# Projeck_telur.net
KiCad netlist of a schematic drawn in EAGLE
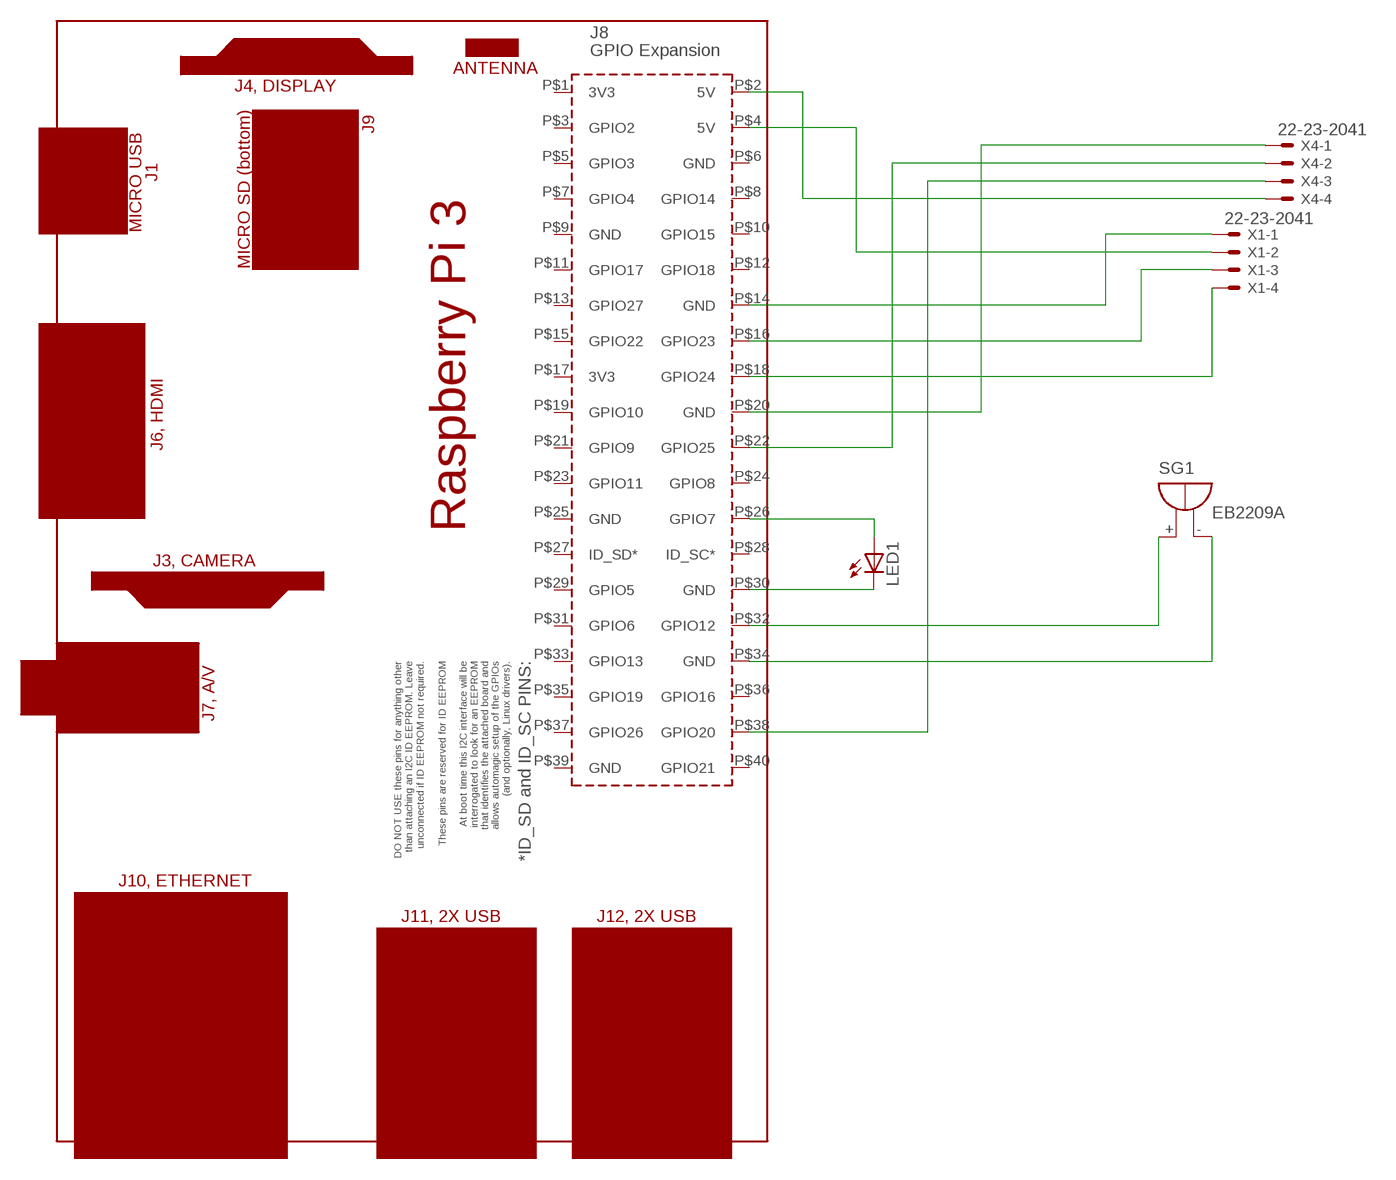
[diagram p0: schematic, sheet 1]

(export (version "E")
  (design (tool "Eeschema 10.0.6"))
  (components
    (comp (ref "LED1")
      (value "LEDB152")
      (footprint "eagle-import:Q62902-B152")
      (libsource (lib "eagle-import") (part "LEDB152"))
    )
    (comp (ref "PCB1")
      (value "RPI3")
      (footprint "eagle-import:RPI3")
      (libsource (lib "eagle-import") (part "RPI3"))
    )
    (comp (ref "SG1")
      (value "EB2209A")
      (footprint "eagle-import:EB2209A")
      (libsource (lib "eagle-import") (part "EB2209A"))
    )
    (comp (ref "X1")
      (value "22-23-2041")
      (footprint "eagle-import:22-23-2041")
      (fields (field (name "MF") "MOLEX"))
      (libsource (lib "eagle-import") (part "22-23-2041"))
    )
    (comp (ref "X4")
      (value "22-23-2041")
      (footprint "eagle-import:22-23-2041")
      (fields (field (name "MF") "MOLEX"))
      (libsource (lib "eagle-import") (part "22-23-2041"))
    )
  )
  (nets
    (net (code "1") (name "Net-(LED1-C)") (class "Default")
      (node (ref "LED1") (pin "K") (pinfunction "C_K") (pintype "passive"))
      (node (ref "PCB1") (pin "P$30") (pinfunction "GND_P$30") (pintype "bidirectional"))
    )
    (net (code "2") (name "Net-(PCB1-GND-PadP$34)") (class "Default")
      (node (ref "PCB1") (pin "P$34") (pinfunction "GND_P$34") (pintype "bidirectional"))
      (node (ref "SG1") (pin "-") (pinfunction "-_-") (pintype "passive"))
    )
    (net (code "3") (name "Net-(PCB1-GPIO7)") (class "Default")
      (node (ref "LED1") (pin "A") (pinfunction "A_A") (pintype "passive"))
      (node (ref "PCB1") (pin "P$26") (pinfunction "GPIO7_P$26") (pintype "bidirectional"))
    )
    (net (code "4") (name "Net-(PCB1-GPIO12)") (class "Default")
      (node (ref "PCB1") (pin "P$32") (pinfunction "GPIO12_P$32") (pintype "bidirectional"))
      (node (ref "SG1") (pin "+") (pinfunction "+_+") (pintype "passive"))
    )
    (net (code "5") (name "Net-(PCB1-GPIO20)") (class "Default")
      (node (ref "PCB1") (pin "P$38") (pinfunction "GPIO20_P$38") (pintype "bidirectional"))
      (node (ref "X4") (pin "3") (pinfunction "S_3") (pintype "passive"))
    )
    (net (code "6") (name "Net-(PCB1-GPIO23)") (class "Default")
      (node (ref "PCB1") (pin "P$16") (pinfunction "GPIO23_P$16") (pintype "bidirectional"))
      (node (ref "X1") (pin "3") (pinfunction "S_3") (pintype "passive"))
    )
    (net (code "7") (name "Net-(PCB1-GPIO24)") (class "Default")
      (node (ref "PCB1") (pin "P$18") (pinfunction "GPIO24_P$18") (pintype "bidirectional"))
      (node (ref "X1") (pin "4") (pinfunction "S_4") (pintype "passive"))
    )
    (net (code "8") (name "Net-(PCB1-GPIO25)") (class "Default")
      (node (ref "PCB1") (pin "P$22") (pinfunction "GPIO25_P$22") (pintype "bidirectional"))
      (node (ref "X4") (pin "2") (pinfunction "S_2") (pintype "passive"))
    )
    (net (code "9") (name "Net-(X1A-S)") (class "Default")
      (node (ref "PCB1") (pin "P$14") (pinfunction "GND_P$14") (pintype "bidirectional"))
      (node (ref "X1") (pin "1") (pinfunction "S_1") (pintype "passive"))
    )
    (net (code "10") (name "Net-(X1B-S)") (class "Default")
      (node (ref "PCB1") (pin "P$4") (pinfunction "5V_P$4") (pintype "bidirectional"))
      (node (ref "X1") (pin "2") (pinfunction "S_2") (pintype "passive"))
    )
    (net (code "11") (name "Net-(X4A-S)") (class "Default")
      (node (ref "PCB1") (pin "P$20") (pinfunction "GND_P$20") (pintype "bidirectional"))
      (node (ref "X4") (pin "1") (pinfunction "S_1") (pintype "passive"))
    )
    (net (code "12") (name "Net-(X4D-S)") (class "Default")
      (node (ref "PCB1") (pin "P$2") (pinfunction "5V_P$2") (pintype "bidirectional"))
      (node (ref "X4") (pin "4") (pinfunction "S_4") (pintype "passive"))
    )
    (net (code "13") (name "unconnected-(PCB1-3V3-PadP$1)") (class "Default")
      (node (ref "PCB1") (pin "P$1") (pinfunction "3V3_P$1") (pintype "bidirectional"))
    )
    (net (code "14") (name "unconnected-(PCB1-3V3-PadP$17)") (class "Default")
      (node (ref "PCB1") (pin "P$17") (pinfunction "3V3_P$17") (pintype "bidirectional"))
    )
    (net (code "15") (name "unconnected-(PCB1-GND-PadP$6)") (class "Default")
      (node (ref "PCB1") (pin "P$6") (pinfunction "GND_P$6") (pintype "bidirectional"))
    )
    (net (code "16") (name "unconnected-(PCB1-GND-PadP$9)") (class "Default")
      (node (ref "PCB1") (pin "P$9") (pinfunction "GND_P$9") (pintype "bidirectional"))
    )
    (net (code "17") (name "unconnected-(PCB1-GND-PadP$25)") (class "Default")
      (node (ref "PCB1") (pin "P$25") (pinfunction "GND_P$25") (pintype "bidirectional"))
    )
    (net (code "18") (name "unconnected-(PCB1-GND-PadP$39)") (class "Default")
      (node (ref "PCB1") (pin "P$39") (pinfunction "GND_P$39") (pintype "bidirectional"))
    )
    (net (code "19") (name "unconnected-(PCB1-GPIO2-PadP$3)") (class "Default")
      (node (ref "PCB1") (pin "P$3") (pinfunction "GPIO2_P$3") (pintype "bidirectional"))
    )
    (net (code "20") (name "unconnected-(PCB1-GPIO3-PadP$5)") (class "Default")
      (node (ref "PCB1") (pin "P$5") (pinfunction "GPIO3_P$5") (pintype "bidirectional"))
    )
    (net (code "21") (name "unconnected-(PCB1-GPIO4-PadP$7)") (class "Default")
      (node (ref "PCB1") (pin "P$7") (pinfunction "GPIO4_P$7") (pintype "bidirectional"))
    )
    (net (code "22") (name "unconnected-(PCB1-GPIO5-PadP$29)") (class "Default")
      (node (ref "PCB1") (pin "P$29") (pinfunction "GPIO5_P$29") (pintype "bidirectional"))
    )
    (net (code "23") (name "unconnected-(PCB1-GPIO6-PadP$31)") (class "Default")
      (node (ref "PCB1") (pin "P$31") (pinfunction "GPIO6_P$31") (pintype "bidirectional"))
    )
    (net (code "24") (name "unconnected-(PCB1-GPIO8-PadP$24)") (class "Default")
      (node (ref "PCB1") (pin "P$24") (pinfunction "GPIO8_P$24") (pintype "bidirectional"))
    )
    (net (code "25") (name "unconnected-(PCB1-GPIO9-PadP$21)") (class "Default")
      (node (ref "PCB1") (pin "P$21") (pinfunction "GPIO9_P$21") (pintype "bidirectional"))
    )
    (net (code "26") (name "unconnected-(PCB1-GPIO10-PadP$19)") (class "Default")
      (node (ref "PCB1") (pin "P$19") (pinfunction "GPIO10_P$19") (pintype "bidirectional"))
    )
    (net (code "27") (name "unconnected-(PCB1-GPIO11-PadP$23)") (class "Default")
      (node (ref "PCB1") (pin "P$23") (pinfunction "GPIO11_P$23") (pintype "bidirectional"))
    )
    (net (code "28") (name "unconnected-(PCB1-GPIO13-PadP$33)") (class "Default")
      (node (ref "PCB1") (pin "P$33") (pinfunction "GPIO13_P$33") (pintype "bidirectional"))
    )
    (net (code "29") (name "unconnected-(PCB1-GPIO14-PadP$8)") (class "Default")
      (node (ref "PCB1") (pin "P$8") (pinfunction "GPIO14_P$8") (pintype "bidirectional"))
    )
    (net (code "30") (name "unconnected-(PCB1-GPIO15-PadP$10)") (class "Default")
      (node (ref "PCB1") (pin "P$10") (pinfunction "GPIO15_P$10") (pintype "bidirectional"))
    )
    (net (code "31") (name "unconnected-(PCB1-GPIO16-PadP$36)") (class "Default")
      (node (ref "PCB1") (pin "P$36") (pinfunction "GPIO16_P$36") (pintype "bidirectional"))
    )
    (net (code "32") (name "unconnected-(PCB1-GPIO17-PadP$11)") (class "Default")
      (node (ref "PCB1") (pin "P$11") (pinfunction "GPIO17_P$11") (pintype "bidirectional"))
    )
    (net (code "33") (name "unconnected-(PCB1-GPIO18-PadP$12)") (class "Default")
      (node (ref "PCB1") (pin "P$12") (pinfunction "GPIO18_P$12") (pintype "bidirectional"))
    )
    (net (code "34") (name "unconnected-(PCB1-GPIO19-PadP$35)") (class "Default")
      (node (ref "PCB1") (pin "P$35") (pinfunction "GPIO19_P$35") (pintype "bidirectional"))
    )
    (net (code "35") (name "unconnected-(PCB1-GPIO21-PadP$40)") (class "Default")
      (node (ref "PCB1") (pin "P$40") (pinfunction "GPIO21_P$40") (pintype "bidirectional"))
    )
    (net (code "36") (name "unconnected-(PCB1-GPIO22-PadP$15)") (class "Default")
      (node (ref "PCB1") (pin "P$15") (pinfunction "GPIO22_P$15") (pintype "bidirectional"))
    )
    (net (code "37") (name "unconnected-(PCB1-GPIO26-PadP$37)") (class "Default")
      (node (ref "PCB1") (pin "P$37") (pinfunction "GPIO26_P$37") (pintype "bidirectional"))
    )
    (net (code "38") (name "unconnected-(PCB1-GPIO27-PadP$13)") (class "Default")
      (node (ref "PCB1") (pin "P$13") (pinfunction "GPIO27_P$13") (pintype "bidirectional"))
    )
    (net (code "39") (name "unconnected-(PCB1-ID_SC*-PadP$28)") (class "Default")
      (node (ref "PCB1") (pin "P$28") (pinfunction "ID_SC*_P$28") (pintype "bidirectional"))
    )
    (net (code "40") (name "unconnected-(PCB1-ID_SD*-PadP$27)") (class "Default")
      (node (ref "PCB1") (pin "P$27") (pinfunction "ID_SD*_P$27") (pintype "bidirectional"))
    )
  )
)
